# Sheet1.net
KiCad netlist of a schematic drawn in Altium Designer
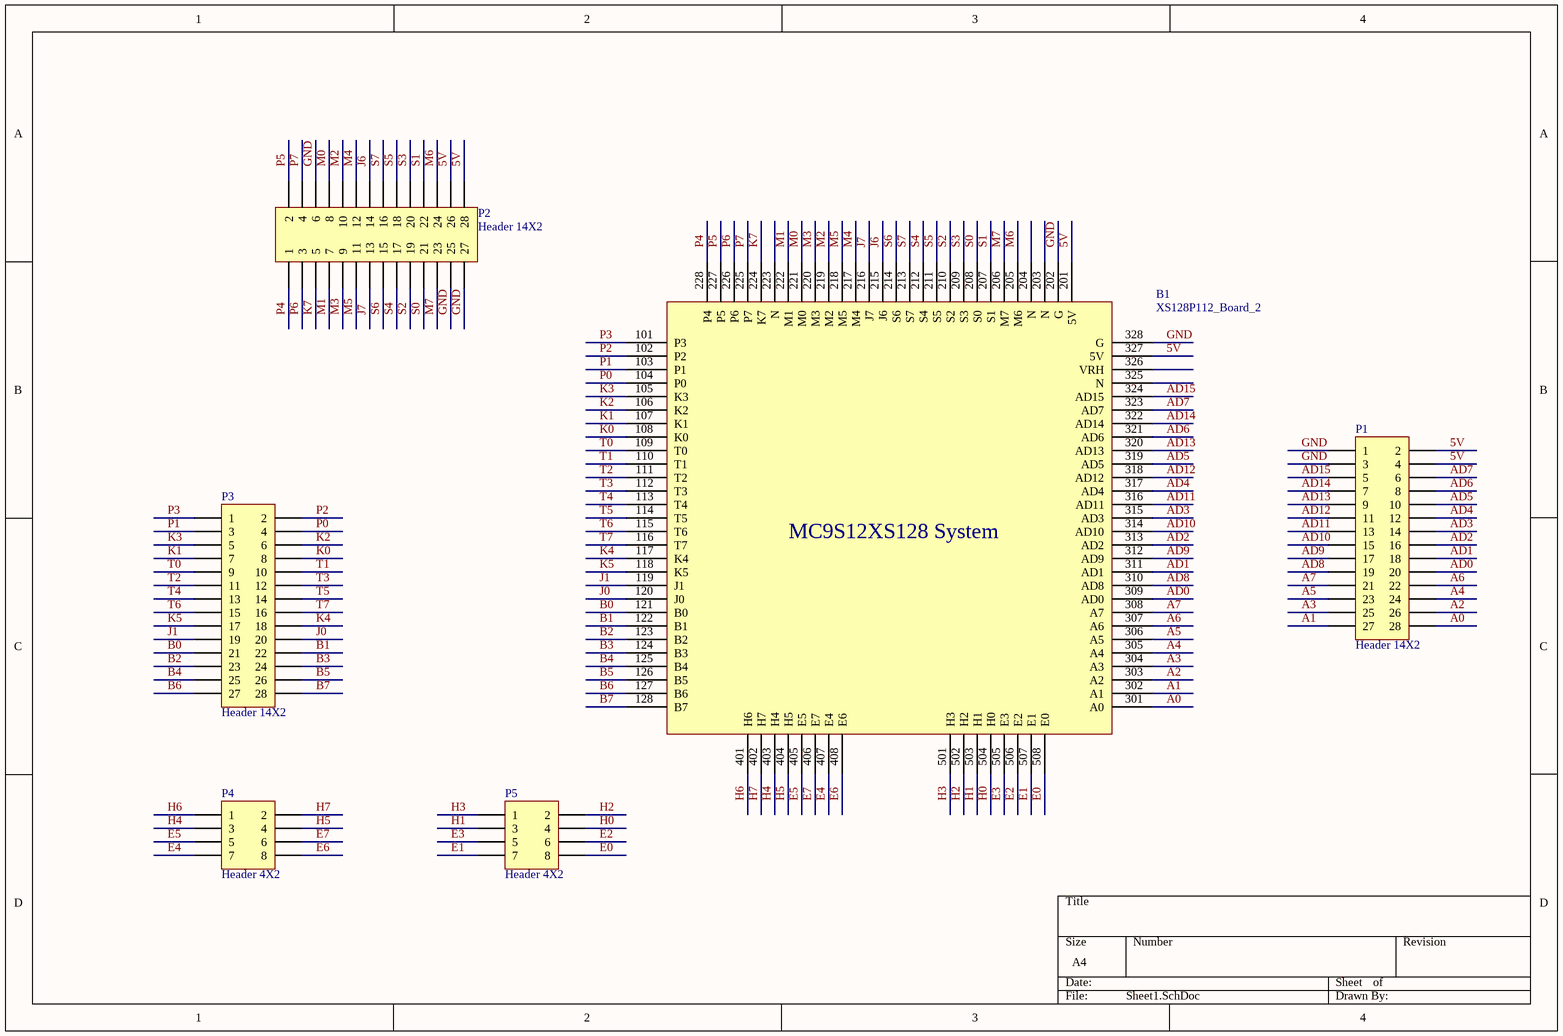
[diagram p0: Sheet1.SchDoc]

(export (version "E")
  (design (tool "Eeschema 10.0.6"))
  (components
    (comp (ref "B1")
      (value "XS128P112_Board_2")
      (footprint "XS128P112_BOARD")
      (libsource (lib "常用1") (part "XS128P112_Board_2"))
    )
    (comp (ref "P1")
      (value "Header 14X2")
      (footprint "HDR2X14")
      (description "Header, 14-Pin, Dual row")
      (fields (field (name "PUBLISHER") "Altium Limited"))
      (libsource (lib "Miscellaneous Connectors") (part "Header 14X2"))
    )
    (comp (ref "P2")
      (value "Header 14X2")
      (footprint "HDR2X14")
      (description "Header, 14-Pin, Dual row")
      (fields (field (name "PUBLISHER") "Altium Limited"))
      (libsource (lib "") (part "Header 14X2_1"))
    )
    (comp (ref "P3")
      (value "Header 14X2")
      (footprint "HDR2X14")
      (description "Header, 14-Pin, Dual row")
      (fields (field (name "PUBLISHER") "Altium Limited"))
      (libsource (lib "Miscellaneous Connectors") (part "Header 14X2"))
    )
    (comp (ref "P4")
      (value "Header 4X2")
      (footprint "HDR2X4")
      (description "Header, 4-Pin, Dual row")
      (fields (field (name "PUBLISHER") "Altium Limited"))
      (libsource (lib "Miscellaneous Connectors") (part "Header 4X2"))
    )
    (comp (ref "P5")
      (value "Header 4X2")
      (footprint "HDR2X4")
      (description "Header, 4-Pin, Dual row")
      (fields (field (name "PUBLISHER") "Altium Limited"))
      (libsource (lib "Miscellaneous Connectors") (part "Header 4X2"))
    )
  )
  (nets
    (net (code "1") (name "/5V") (class "Default")
      (node (ref "B1") (pin "201") (pinfunction "5V_201") (pintype "passive"))
      (node (ref "B1") (pin "327") (pinfunction "5V_327") (pintype "passive"))
      (node (ref "P1") (pin "2") (pinfunction "2_2") (pintype "passive"))
      (node (ref "P1") (pin "4") (pinfunction "4_4") (pintype "passive"))
      (node (ref "P2") (pin "26") (pinfunction "26_26") (pintype "passive"))
      (node (ref "P2") (pin "28") (pinfunction "28_28") (pintype "passive"))
    )
    (net (code "2") (name "/A0") (class "Default")
      (node (ref "B1") (pin "301") (pinfunction "A0_301") (pintype "passive"))
      (node (ref "P1") (pin "28") (pinfunction "28_28") (pintype "passive"))
    )
    (net (code "3") (name "/A1") (class "Default")
      (node (ref "B1") (pin "302") (pinfunction "A1_302") (pintype "passive"))
      (node (ref "P1") (pin "27") (pinfunction "27_27") (pintype "passive"))
    )
    (net (code "4") (name "/A2") (class "Default")
      (node (ref "B1") (pin "303") (pinfunction "A2_303") (pintype "passive"))
      (node (ref "P1") (pin "26") (pinfunction "26_26") (pintype "passive"))
    )
    (net (code "5") (name "/A3") (class "Default")
      (node (ref "B1") (pin "304") (pinfunction "A3_304") (pintype "passive"))
      (node (ref "P1") (pin "25") (pinfunction "25_25") (pintype "passive"))
    )
    (net (code "6") (name "/A4") (class "Default")
      (node (ref "B1") (pin "305") (pinfunction "A4_305") (pintype "passive"))
      (node (ref "P1") (pin "24") (pinfunction "24_24") (pintype "passive"))
    )
    (net (code "7") (name "/A5") (class "Default")
      (node (ref "B1") (pin "306") (pinfunction "A5_306") (pintype "passive"))
      (node (ref "P1") (pin "23") (pinfunction "23_23") (pintype "passive"))
    )
    (net (code "8") (name "/A6") (class "Default")
      (node (ref "B1") (pin "307") (pinfunction "A6_307") (pintype "passive"))
      (node (ref "P1") (pin "22") (pinfunction "22_22") (pintype "passive"))
    )
    (net (code "9") (name "/A7") (class "Default")
      (node (ref "B1") (pin "308") (pinfunction "A7_308") (pintype "passive"))
      (node (ref "P1") (pin "21") (pinfunction "21_21") (pintype "passive"))
    )
    (net (code "10") (name "/AD0") (class "Default")
      (node (ref "B1") (pin "309") (pinfunction "AD0_309") (pintype "passive"))
      (node (ref "P1") (pin "20") (pinfunction "20_20") (pintype "passive"))
    )
    (net (code "11") (name "/AD1") (class "Default")
      (node (ref "B1") (pin "311") (pinfunction "AD1_311") (pintype "passive"))
      (node (ref "P1") (pin "18") (pinfunction "18_18") (pintype "passive"))
    )
    (net (code "12") (name "/AD2") (class "Default")
      (node (ref "B1") (pin "313") (pinfunction "AD2_313") (pintype "passive"))
      (node (ref "P1") (pin "16") (pinfunction "16_16") (pintype "passive"))
    )
    (net (code "13") (name "/AD3") (class "Default")
      (node (ref "B1") (pin "315") (pinfunction "AD3_315") (pintype "passive"))
      (node (ref "P1") (pin "14") (pinfunction "14_14") (pintype "passive"))
    )
    (net (code "14") (name "/AD4") (class "Default")
      (node (ref "B1") (pin "317") (pinfunction "AD4_317") (pintype "passive"))
      (node (ref "P1") (pin "12") (pinfunction "12_12") (pintype "passive"))
    )
    (net (code "15") (name "/AD5") (class "Default")
      (node (ref "B1") (pin "319") (pinfunction "AD5_319") (pintype "passive"))
      (node (ref "P1") (pin "10") (pinfunction "10_10") (pintype "passive"))
    )
    (net (code "16") (name "/AD6") (class "Default")
      (node (ref "B1") (pin "321") (pinfunction "AD6_321") (pintype "passive"))
      (node (ref "P1") (pin "8") (pinfunction "8_8") (pintype "passive"))
    )
    (net (code "17") (name "/AD7") (class "Default")
      (node (ref "B1") (pin "323") (pinfunction "AD7_323") (pintype "passive"))
      (node (ref "P1") (pin "6") (pinfunction "6_6") (pintype "passive"))
    )
    (net (code "18") (name "/AD8") (class "Default")
      (node (ref "B1") (pin "310") (pinfunction "AD8_310") (pintype "passive"))
      (node (ref "P1") (pin "19") (pinfunction "19_19") (pintype "passive"))
    )
    (net (code "19") (name "/AD9") (class "Default")
      (node (ref "B1") (pin "312") (pinfunction "AD9_312") (pintype "passive"))
      (node (ref "P1") (pin "17") (pinfunction "17_17") (pintype "passive"))
    )
    (net (code "20") (name "/AD10") (class "Default")
      (node (ref "B1") (pin "314") (pinfunction "AD10_314") (pintype "passive"))
      (node (ref "P1") (pin "15") (pinfunction "15_15") (pintype "passive"))
    )
    (net (code "21") (name "/AD11") (class "Default")
      (node (ref "B1") (pin "316") (pinfunction "AD11_316") (pintype "passive"))
      (node (ref "P1") (pin "13") (pinfunction "13_13") (pintype "passive"))
    )
    (net (code "22") (name "/AD12") (class "Default")
      (node (ref "B1") (pin "318") (pinfunction "AD12_318") (pintype "passive"))
      (node (ref "P1") (pin "11") (pinfunction "11_11") (pintype "passive"))
    )
    (net (code "23") (name "/AD13") (class "Default")
      (node (ref "B1") (pin "320") (pinfunction "AD13_320") (pintype "passive"))
      (node (ref "P1") (pin "9") (pinfunction "9_9") (pintype "passive"))
    )
    (net (code "24") (name "/AD14") (class "Default")
      (node (ref "B1") (pin "322") (pinfunction "AD14_322") (pintype "passive"))
      (node (ref "P1") (pin "7") (pinfunction "7_7") (pintype "passive"))
    )
    (net (code "25") (name "/AD15") (class "Default")
      (node (ref "B1") (pin "324") (pinfunction "AD15_324") (pintype "passive"))
      (node (ref "P1") (pin "5") (pinfunction "5_5") (pintype "passive"))
    )
    (net (code "26") (name "/B0") (class "Default")
      (node (ref "B1") (pin "121") (pinfunction "B0_121") (pintype "passive"))
      (node (ref "P3") (pin "21") (pinfunction "21_21") (pintype "passive"))
    )
    (net (code "27") (name "/B1") (class "Default")
      (node (ref "B1") (pin "122") (pinfunction "B1_122") (pintype "passive"))
      (node (ref "P3") (pin "22") (pinfunction "22_22") (pintype "passive"))
    )
    (net (code "28") (name "/B2") (class "Default")
      (node (ref "B1") (pin "123") (pinfunction "B2_123") (pintype "passive"))
      (node (ref "P3") (pin "23") (pinfunction "23_23") (pintype "passive"))
    )
    (net (code "29") (name "/B3") (class "Default")
      (node (ref "B1") (pin "124") (pinfunction "B3_124") (pintype "passive"))
      (node (ref "P3") (pin "24") (pinfunction "24_24") (pintype "passive"))
    )
    (net (code "30") (name "/B4") (class "Default")
      (node (ref "B1") (pin "125") (pinfunction "B4_125") (pintype "passive"))
      (node (ref "P3") (pin "25") (pinfunction "25_25") (pintype "passive"))
    )
    (net (code "31") (name "/B5") (class "Default")
      (node (ref "B1") (pin "126") (pinfunction "B5_126") (pintype "passive"))
      (node (ref "P3") (pin "26") (pinfunction "26_26") (pintype "passive"))
    )
    (net (code "32") (name "/B6") (class "Default")
      (node (ref "B1") (pin "127") (pinfunction "B6_127") (pintype "passive"))
      (node (ref "P3") (pin "27") (pinfunction "27_27") (pintype "passive"))
    )
    (net (code "33") (name "/B7") (class "Default")
      (node (ref "B1") (pin "128") (pinfunction "B7_128") (pintype "passive"))
      (node (ref "P3") (pin "28") (pinfunction "28_28") (pintype "passive"))
    )
    (net (code "34") (name "/E0") (class "Default")
      (node (ref "B1") (pin "508") (pinfunction "E0_508") (pintype "passive"))
      (node (ref "P5") (pin "8") (pinfunction "8_8") (pintype "passive"))
    )
    (net (code "35") (name "/E1") (class "Default")
      (node (ref "B1") (pin "507") (pinfunction "E1_507") (pintype "passive"))
      (node (ref "P5") (pin "7") (pinfunction "7_7") (pintype "passive"))
    )
    (net (code "36") (name "/E2") (class "Default")
      (node (ref "B1") (pin "506") (pinfunction "E2_506") (pintype "passive"))
      (node (ref "P5") (pin "6") (pinfunction "6_6") (pintype "passive"))
    )
    (net (code "37") (name "/E3") (class "Default")
      (node (ref "B1") (pin "505") (pinfunction "E3_505") (pintype "passive"))
      (node (ref "P5") (pin "5") (pinfunction "5_5") (pintype "passive"))
    )
    (net (code "38") (name "/E4") (class "Default")
      (node (ref "B1") (pin "407") (pinfunction "E4_407") (pintype "passive"))
      (node (ref "P4") (pin "7") (pinfunction "7_7") (pintype "passive"))
    )
    (net (code "39") (name "/E5") (class "Default")
      (node (ref "B1") (pin "405") (pinfunction "E5_405") (pintype "passive"))
      (node (ref "P4") (pin "5") (pinfunction "5_5") (pintype "passive"))
    )
    (net (code "40") (name "/E6") (class "Default")
      (node (ref "B1") (pin "408") (pinfunction "E6_408") (pintype "passive"))
      (node (ref "P4") (pin "8") (pinfunction "8_8") (pintype "passive"))
    )
    (net (code "41") (name "/E7") (class "Default")
      (node (ref "B1") (pin "406") (pinfunction "E7_406") (pintype "passive"))
      (node (ref "P4") (pin "6") (pinfunction "6_6") (pintype "passive"))
    )
    (net (code "42") (name "/GND") (class "Default")
      (node (ref "B1") (pin "202") (pinfunction "G_202") (pintype "passive"))
      (node (ref "B1") (pin "328") (pinfunction "G_328") (pintype "passive"))
      (node (ref "P1") (pin "1") (pinfunction "1_1") (pintype "passive"))
      (node (ref "P1") (pin "3") (pinfunction "3_3") (pintype "passive"))
      (node (ref "P2") (pin "25") (pinfunction "25_25") (pintype "passive"))
      (node (ref "P2") (pin "27") (pinfunction "27_27") (pintype "passive"))
      (node (ref "P2") (pin "6") (pinfunction "6_6") (pintype "passive"))
    )
    (net (code "43") (name "/H0") (class "Default")
      (node (ref "B1") (pin "504") (pinfunction "H0_504") (pintype "passive"))
      (node (ref "P5") (pin "4") (pinfunction "4_4") (pintype "passive"))
    )
    (net (code "44") (name "/H1") (class "Default")
      (node (ref "B1") (pin "503") (pinfunction "H1_503") (pintype "passive"))
      (node (ref "P5") (pin "3") (pinfunction "3_3") (pintype "passive"))
    )
    (net (code "45") (name "/H2") (class "Default")
      (node (ref "B1") (pin "502") (pinfunction "H2_502") (pintype "passive"))
      (node (ref "P5") (pin "2") (pinfunction "2_2") (pintype "passive"))
    )
    (net (code "46") (name "/H3") (class "Default")
      (node (ref "B1") (pin "501") (pinfunction "H3_501") (pintype "passive"))
      (node (ref "P5") (pin "1") (pinfunction "1_1") (pintype "passive"))
    )
    (net (code "47") (name "/H4") (class "Default")
      (node (ref "B1") (pin "403") (pinfunction "H4_403") (pintype "passive"))
      (node (ref "P4") (pin "3") (pinfunction "3_3") (pintype "passive"))
    )
    (net (code "48") (name "/H5") (class "Default")
      (node (ref "B1") (pin "404") (pinfunction "H5_404") (pintype "passive"))
      (node (ref "P4") (pin "4") (pinfunction "4_4") (pintype "passive"))
    )
    (net (code "49") (name "/H6") (class "Default")
      (node (ref "B1") (pin "401") (pinfunction "H6_401") (pintype "passive"))
      (node (ref "P4") (pin "1") (pinfunction "1_1") (pintype "passive"))
    )
    (net (code "50") (name "/H7") (class "Default")
      (node (ref "B1") (pin "402") (pinfunction "H7_402") (pintype "passive"))
      (node (ref "P4") (pin "2") (pinfunction "2_2") (pintype "passive"))
    )
    (net (code "51") (name "/J0") (class "Default")
      (node (ref "B1") (pin "120") (pinfunction "J0_120") (pintype "passive"))
      (node (ref "P3") (pin "20") (pinfunction "20_20") (pintype "passive"))
    )
    (net (code "52") (name "/J1") (class "Default")
      (node (ref "B1") (pin "119") (pinfunction "J1_119") (pintype "passive"))
      (node (ref "P3") (pin "19") (pinfunction "19_19") (pintype "passive"))
    )
    (net (code "53") (name "/J6") (class "Default")
      (node (ref "B1") (pin "215") (pinfunction "J6_215") (pintype "passive"))
      (node (ref "P2") (pin "14") (pinfunction "14_14") (pintype "passive"))
    )
    (net (code "54") (name "/J7") (class "Default")
      (node (ref "B1") (pin "216") (pinfunction "J7_216") (pintype "passive"))
      (node (ref "P2") (pin "13") (pinfunction "13_13") (pintype "passive"))
    )
    (net (code "55") (name "/K0") (class "Default")
      (node (ref "B1") (pin "108") (pinfunction "K0_108") (pintype "passive"))
      (node (ref "P3") (pin "8") (pinfunction "8_8") (pintype "passive"))
    )
    (net (code "56") (name "/K1") (class "Default")
      (node (ref "B1") (pin "107") (pinfunction "K1_107") (pintype "passive"))
      (node (ref "P3") (pin "7") (pinfunction "7_7") (pintype "passive"))
    )
    (net (code "57") (name "/K2") (class "Default")
      (node (ref "B1") (pin "106") (pinfunction "K2_106") (pintype "passive"))
      (node (ref "P3") (pin "6") (pinfunction "6_6") (pintype "passive"))
    )
    (net (code "58") (name "/K3") (class "Default")
      (node (ref "B1") (pin "105") (pinfunction "K3_105") (pintype "passive"))
      (node (ref "P3") (pin "5") (pinfunction "5_5") (pintype "passive"))
    )
    (net (code "59") (name "/K4") (class "Default")
      (node (ref "B1") (pin "117") (pinfunction "K4_117") (pintype "passive"))
      (node (ref "P3") (pin "18") (pinfunction "18_18") (pintype "passive"))
    )
    (net (code "60") (name "/K5") (class "Default")
      (node (ref "B1") (pin "118") (pinfunction "K5_118") (pintype "passive"))
      (node (ref "P3") (pin "17") (pinfunction "17_17") (pintype "passive"))
    )
    (net (code "61") (name "/K7") (class "Default")
      (node (ref "B1") (pin "224") (pinfunction "K7_224") (pintype "passive"))
      (node (ref "P2") (pin "5") (pinfunction "5_5") (pintype "passive"))
    )
    (net (code "62") (name "/M0") (class "Default")
      (node (ref "B1") (pin "221") (pinfunction "M0_221") (pintype "passive"))
      (node (ref "P2") (pin "8") (pinfunction "8_8") (pintype "passive"))
    )
    (net (code "63") (name "/M1") (class "Default")
      (node (ref "B1") (pin "222") (pinfunction "M1_222") (pintype "passive"))
      (node (ref "P2") (pin "7") (pinfunction "7_7") (pintype "passive"))
    )
    (net (code "64") (name "/M2") (class "Default")
      (node (ref "B1") (pin "219") (pinfunction "M2_219") (pintype "passive"))
      (node (ref "P2") (pin "10") (pinfunction "10_10") (pintype "passive"))
    )
    (net (code "65") (name "/M3") (class "Default")
      (node (ref "B1") (pin "220") (pinfunction "M3_220") (pintype "passive"))
      (node (ref "P2") (pin "9") (pinfunction "9_9") (pintype "passive"))
    )
    (net (code "66") (name "/M4") (class "Default")
      (node (ref "B1") (pin "217") (pinfunction "M4_217") (pintype "passive"))
      (node (ref "P2") (pin "12") (pinfunction "12_12") (pintype "passive"))
    )
    (net (code "67") (name "/M5") (class "Default")
      (node (ref "B1") (pin "218") (pinfunction "M5_218") (pintype "passive"))
      (node (ref "P2") (pin "11") (pinfunction "11_11") (pintype "passive"))
    )
    (net (code "68") (name "/M6") (class "Default")
      (node (ref "B1") (pin "205") (pinfunction "M6_205") (pintype "passive"))
      (node (ref "P2") (pin "24") (pinfunction "24_24") (pintype "passive"))
    )
    (net (code "69") (name "/M7") (class "Default")
      (node (ref "B1") (pin "206") (pinfunction "M7_206") (pintype "passive"))
      (node (ref "P2") (pin "23") (pinfunction "23_23") (pintype "passive"))
    )
    (net (code "70") (name "/P0") (class "Default")
      (node (ref "B1") (pin "104") (pinfunction "P0_104") (pintype "passive"))
      (node (ref "P3") (pin "4") (pinfunction "4_4") (pintype "passive"))
    )
    (net (code "71") (name "/P1") (class "Default")
      (node (ref "B1") (pin "103") (pinfunction "P1_103") (pintype "passive"))
      (node (ref "P3") (pin "3") (pinfunction "3_3") (pintype "passive"))
    )
    (net (code "72") (name "/P2") (class "Default")
      (node (ref "B1") (pin "102") (pinfunction "P2_102") (pintype "passive"))
      (node (ref "P3") (pin "2") (pinfunction "2_2") (pintype "passive"))
    )
    (net (code "73") (name "/P3") (class "Default")
      (node (ref "B1") (pin "101") (pinfunction "P3_101") (pintype "passive"))
      (node (ref "P3") (pin "1") (pinfunction "1_1") (pintype "passive"))
    )
    (net (code "74") (name "/P4") (class "Default")
      (node (ref "B1") (pin "228") (pinfunction "P4_228") (pintype "passive"))
      (node (ref "P2") (pin "1") (pinfunction "1_1") (pintype "passive"))
    )
    (net (code "75") (name "/P5") (class "Default")
      (node (ref "B1") (pin "227") (pinfunction "P5_227") (pintype "passive"))
      (node (ref "P2") (pin "2") (pinfunction "2_2") (pintype "passive"))
    )
    (net (code "76") (name "/P6") (class "Default")
      (node (ref "B1") (pin "226") (pinfunction "P6_226") (pintype "passive"))
      (node (ref "P2") (pin "3") (pinfunction "3_3") (pintype "passive"))
    )
    (net (code "77") (name "/P7") (class "Default")
      (node (ref "B1") (pin "225") (pinfunction "P7_225") (pintype "passive"))
      (node (ref "P2") (pin "4") (pinfunction "4_4") (pintype "passive"))
    )
    (net (code "78") (name "/S0") (class "Default")
      (node (ref "B1") (pin "208") (pinfunction "S0_208") (pintype "passive"))
      (node (ref "P2") (pin "21") (pinfunction "21_21") (pintype "passive"))
    )
    (net (code "79") (name "/S1") (class "Default")
      (node (ref "B1") (pin "207") (pinfunction "S1_207") (pintype "passive"))
      (node (ref "P2") (pin "22") (pinfunction "22_22") (pintype "passive"))
    )
    (net (code "80") (name "/S2") (class "Default")
      (node (ref "B1") (pin "210") (pinfunction "S2_210") (pintype "passive"))
      (node (ref "P2") (pin "19") (pinfunction "19_19") (pintype "passive"))
    )
    (net (code "81") (name "/S3") (class "Default")
      (node (ref "B1") (pin "209") (pinfunction "S3_209") (pintype "passive"))
      (node (ref "P2") (pin "20") (pinfunction "20_20") (pintype "passive"))
    )
    (net (code "82") (name "/S4") (class "Default")
      (node (ref "B1") (pin "212") (pinfunction "S4_212") (pintype "passive"))
      (node (ref "P2") (pin "17") (pinfunction "17_17") (pintype "passive"))
    )
    (net (code "83") (name "/S5") (class "Default")
      (node (ref "B1") (pin "211") (pinfunction "S5_211") (pintype "passive"))
      (node (ref "P2") (pin "18") (pinfunction "18_18") (pintype "passive"))
    )
    (net (code "84") (name "/S6") (class "Default")
      (node (ref "B1") (pin "214") (pinfunction "S6_214") (pintype "passive"))
      (node (ref "P2") (pin "15") (pinfunction "15_15") (pintype "passive"))
    )
    (net (code "85") (name "/S7") (class "Default")
      (node (ref "B1") (pin "213") (pinfunction "S7_213") (pintype "passive"))
      (node (ref "P2") (pin "16") (pinfunction "16_16") (pintype "passive"))
    )
    (net (code "86") (name "/T0") (class "Default")
      (node (ref "B1") (pin "109") (pinfunction "T0_109") (pintype "passive"))
      (node (ref "P3") (pin "9") (pinfunction "9_9") (pintype "passive"))
    )
    (net (code "87") (name "/T1") (class "Default")
      (node (ref "B1") (pin "110") (pinfunction "T1_110") (pintype "passive"))
      (node (ref "P3") (pin "10") (pinfunction "10_10") (pintype "passive"))
    )
    (net (code "88") (name "/T2") (class "Default")
      (node (ref "B1") (pin "111") (pinfunction "T2_111") (pintype "passive"))
      (node (ref "P3") (pin "11") (pinfunction "11_11") (pintype "passive"))
    )
    (net (code "89") (name "/T3") (class "Default")
      (node (ref "B1") (pin "112") (pinfunction "T3_112") (pintype "passive"))
      (node (ref "P3") (pin "12") (pinfunction "12_12") (pintype "passive"))
    )
    (net (code "90") (name "/T4") (class "Default")
      (node (ref "B1") (pin "113") (pinfunction "T4_113") (pintype "passive"))
      (node (ref "P3") (pin "13") (pinfunction "13_13") (pintype "passive"))
    )
    (net (code "91") (name "/T5") (class "Default")
      (node (ref "B1") (pin "114") (pinfunction "T5_114") (pintype "passive"))
      (node (ref "P3") (pin "14") (pinfunction "14_14") (pintype "passive"))
    )
    (net (code "92") (name "/T6") (class "Default")
      (node (ref "B1") (pin "115") (pinfunction "T6_115") (pintype "passive"))
      (node (ref "P3") (pin "15") (pinfunction "15_15") (pintype "passive"))
    )
    (net (code "93") (name "/T7") (class "Default")
      (node (ref "B1") (pin "116") (pinfunction "T7_116") (pintype "passive"))
      (node (ref "P3") (pin "16") (pinfunction "16_16") (pintype "passive"))
    )
    (net (code "94") (name "unconnected-(B1-N-Pad203)") (class "Default")
      (node (ref "B1") (pin "203") (pinfunction "N_203") (pintype "passive"))
    )
    (net (code "95") (name "unconnected-(B1-N-Pad204)") (class "Default")
      (node (ref "B1") (pin "204") (pinfunction "N_204") (pintype "passive"))
    )
    (net (code "96") (name "unconnected-(B1-N-Pad223)") (class "Default")
      (node (ref "B1") (pin "223") (pinfunction "N_223") (pintype "passive"))
    )
    (net (code "97") (name "unconnected-(B1-N-Pad325)") (class "Default")
      (node (ref "B1") (pin "325") (pinfunction "N_325") (pintype "passive"))
    )
    (net (code "98") (name "unconnected-(B1-VRH-Pad326)") (class "Default")
      (node (ref "B1") (pin "326") (pinfunction "VRH_326") (pintype "passive"))
    )
  )
)
